# CAN.net
KiCad netlist of a schematic drawn in Altium Designer
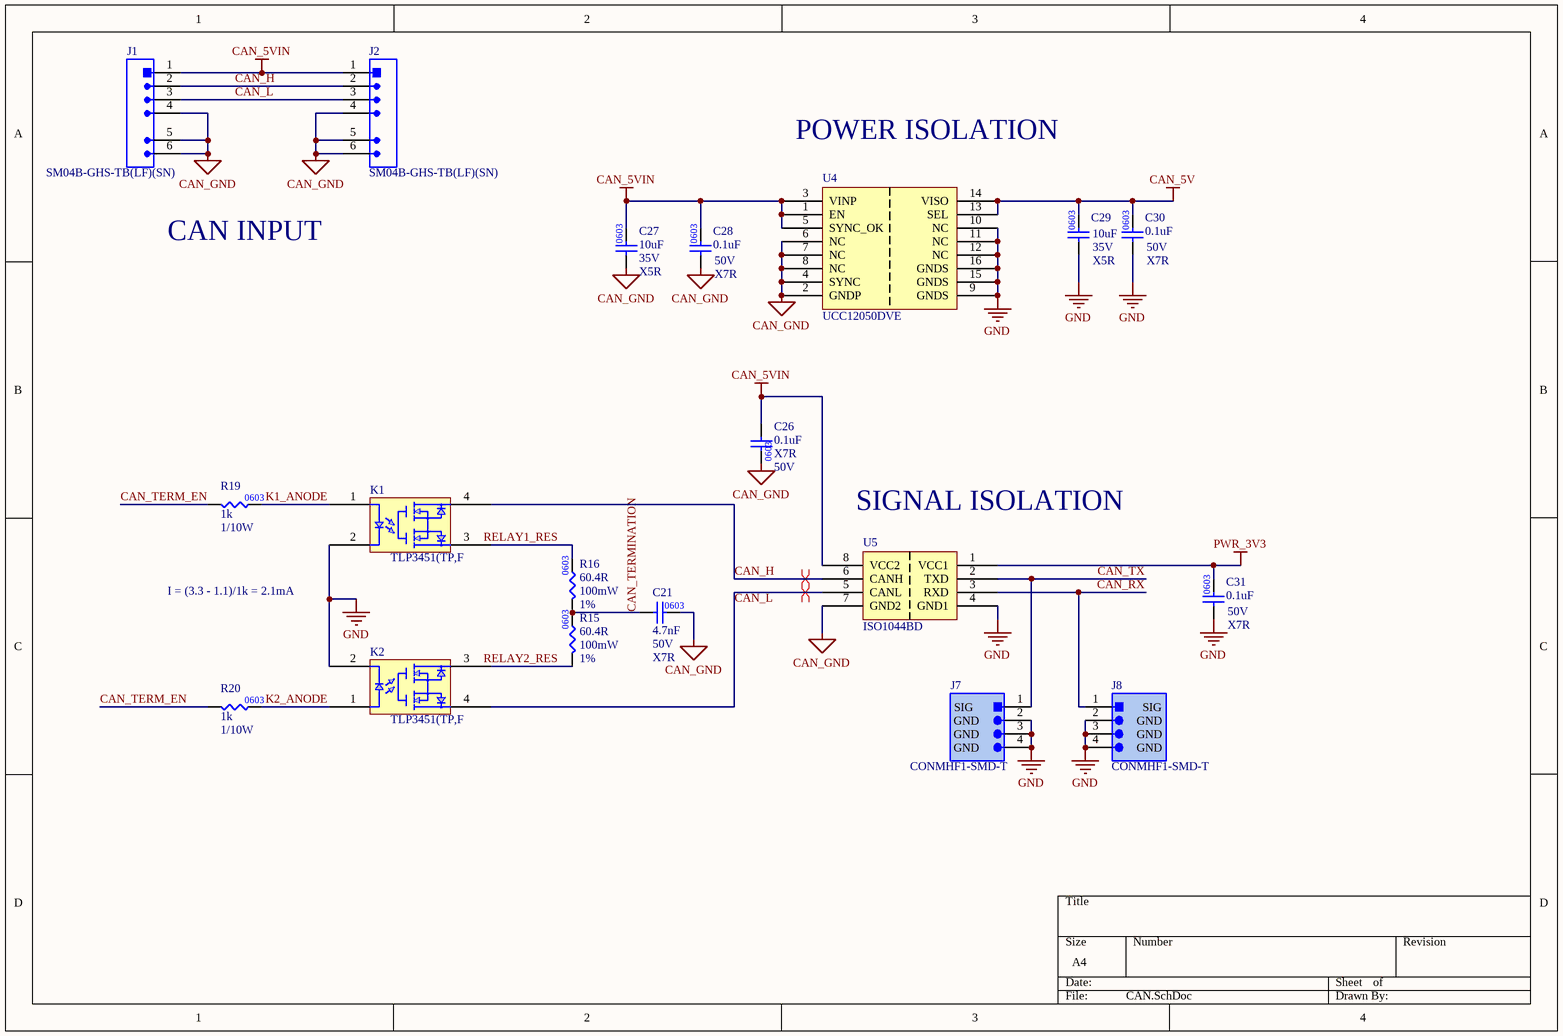
[diagram p0: CAN.SchDoc]

(export (version "E")
  (design (tool "Eeschema 10.0.6"))
  (components
    (comp (ref "C21")
      (value "4.7nF")
      (footprint ".CAP_0603-Footprint-1")
      (description "CAP CER 4700PF 50V X7R 0603")
      (fields
        (field (name "RATED DC VOLTAGE (URDC)") "50V")
        (field (name "TEMPERATURE CHARACTERISTICS CODE") "X7R")
        (field (name "Comment") "GCM188R71H472KA37D")
      )
      (libsource (lib "WARG") (part ".CAP_0603-Symbol-1"))
    )
    (comp (ref "C26")
      (value "0.1uF")
      (footprint ".CAP_0603-Footprint-1")
      (description "CAP CER 0.1uF 50V X7R 0603")
      (fields
        (field (name "DIELECTRIC") "X7R")
        (field (name "VOLTAGE") "50V")
        (field (name "TOLERANCE") "10%")
        (field (name "Comment") "GCM188R71H104KA57D")
      )
      (libsource (lib "WARG") (part ".CAP_0603-Symbol-1"))
    )
    (comp (ref "C27")
      (value "GRM188R6YA106MA73D")
      (footprint ".CAP_0603-Footprint-1")
      (description "CAP CER 10UF 35V X5R 0603")
      (fields
        (field (name "TOLERANCE") "±20%")
        (field (name "CAPACITANCE") "10uF")
        (field (name "VOLTAGE") "35V")
        (field (name "TEMPERATURE COEFFICIENT") "X5R")
      )
      (libsource (lib "WARG") (part ".CAP_0603-Symbol-1"))
    )
    (comp (ref "C28")
      (value "0.1uF")
      (footprint ".CAP_0603-Footprint-1")
      (description "CAP CER 0.1uF 50V X7R 0603")
      (fields
        (field (name "DIELECTRIC") "X7R")
        (field (name "VOLTAGE") "50V")
        (field (name "TOLERANCE") "10%")
        (field (name "Comment") "GCM188R71H104KA57D")
      )
      (libsource (lib "WARG") (part ".CAP_0603-Symbol-1"))
    )
    (comp (ref "C29")
      (value "GRM188R6YA106MA73D")
      (footprint ".CAP_0603-Footprint-1")
      (description "CAP CER 10UF 35V X5R 0603")
      (fields
        (field (name "TOLERANCE") "±20%")
        (field (name "CAPACITANCE") "10uF")
        (field (name "VOLTAGE") "35V")
        (field (name "TEMPERATURE COEFFICIENT") "X5R")
      )
      (libsource (lib "WARG") (part ".CAP_0603-Symbol-1"))
    )
    (comp (ref "C30")
      (value "0.1uF")
      (footprint ".CAP_0603-Footprint-1")
      (description "CAP CER 0.1uF 50V X7R 0603")
      (fields
        (field (name "DIELECTRIC") "X7R")
        (field (name "VOLTAGE") "50V")
        (field (name "TOLERANCE") "10%")
        (field (name "Comment") "GCM188R71H104KA57D")
      )
      (libsource (lib "WARG") (part ".CAP_0603-Symbol-1"))
    )
    (comp (ref "C31")
      (value "0.1uF")
      (footprint ".CAP_0603-Footprint-1")
      (description "CAP CER 0.1uF 50V X7R 0603")
      (fields
        (field (name "DIELECTRIC") "X7R")
        (field (name "VOLTAGE") "50V")
        (field (name "TOLERANCE") "10%")
        (field (name "Comment") "GCM188R71H104KA57D")
      )
      (libsource (lib "WARG") (part ".CAP_0603-Symbol-1"))
    )
    (comp (ref "J1")
      (value "SM04B-GHS-TB(LF)(SN)")
      (footprint "CONN_SM04B-GHS-TB_JST")
      (description "Conn Shrouded Header HDR 4 POS 1.25mm Solder RA SMD Reel")
      (libsource (lib "WARG") (part "SM04B-GHS-TB(LF)(SN)"))
    )
    (comp (ref "J2")
      (value "SM04B-GHS-TB(LF)(SN)")
      (footprint "CONN_SM04B-GHS-TB_JST")
      (description "Conn Shrouded Header HDR 4 POS 1.25mm Solder RA SMD Reel")
      (libsource (lib "") (part "SM04B-GHS-TB(LF)(SN)_1"))
    )
    (comp (ref "J7")
      (value "CONMHF1-SMD-T")
      (footprint "CONMHF1-SMD-T-Footprint-1")
      (description "CONN UMC JACK STR SMD")
      (libsource (lib "WARG") (part "CONMHF1-SMD-T-Symbol-1"))
    )
    (comp (ref "J8")
      (value "CONMHF1-SMD-T")
      (footprint "CONMHF1-SMD-T-Footprint-1")
      (description "CONN UMC JACK STR SMD")
      (libsource (lib "") (part "CONMHF1-SMD-T-Symbol-1_1"))
    )
    (comp (ref "K1")
      (value "TLP3451(TP,F")
      (footprint "TLP3451(TP,F-Footprint-1")
      (description "Solid State Relay 20MA 1.4V Dc-in Ac/dc-out 4-PIN Vson T/r")
      (libsource (lib "WARG") (part "TLP3451(TP,F-Symbol-1"))
    )
    (comp (ref "K2")
      (value "TLP3451(TP,F")
      (footprint "TLP3451(TP,F-Footprint-1")
      (description "Solid State Relay 20MA 1.4V Dc-in Ac/dc-out 4-PIN Vson T/r")
      (libsource (lib "WARG") (part "TLP3451(TP,F-Symbol-1"))
    )
    (comp (ref "R15")
      (value "60.4R")
      (footprint "RES0603")
      (description "RES 60.4 OHM 1% 1/10W 0603")
      (fields
        (field (name "TOLERANCE") "1%")
        (field (name "POWER") "100mW")
        (field (name "Comment") "RC0603FR-1360R4L")
      )
      (libsource (lib "WARG") (part "RES-2"))
    )
    (comp (ref "R16")
      (value "60.4R")
      (footprint "RES0603")
      (description "RES 60.4 OHM 1% 1/10W 0603")
      (fields
        (field (name "TOLERANCE") "1%")
        (field (name "POWER") "100mW")
        (field (name "Comment") "RC0603FR-1360R4L")
      )
      (libsource (lib "WARG") (part "RES-2"))
    )
    (comp (ref "R19")
      (value "1k")
      (footprint ".RES_0603-Footprint-1")
      (description "RES 1k OHM 1% 1/10W 0603")
      (fields
        (field (name "POWER") "1/10W")
        (field (name "TOLERANCE") "1%")
        (field (name "Comment") "RC0603FR-071KL")
      )
      (libsource (lib "WARG") (part ".RES_0603-Symbol-1"))
    )
    (comp (ref "R20")
      (value "1k")
      (footprint ".RES_0603-Footprint-1")
      (description "RES 1k OHM 1% 1/10W 0603")
      (fields
        (field (name "POWER") "1/10W")
        (field (name "TOLERANCE") "1%")
        (field (name "Comment") "RC0603FR-071KL")
      )
      (libsource (lib "WARG") (part ".RES_0603-Symbol-1"))
    )
    (comp (ref "U4")
      (value "UCC12050DVE")
      (footprint "16SOIC-Footprint")
      (description "DC DC CONVERTER 3.3V 5V 500MW")
      (libsource (lib "WARG") (part "UCC12050DVE-Symbol-1"))
    )
    (comp (ref "U5")
      (value "ISO1044BD")
      (footprint "8SOIC-Footprint-1")
      (description "Isolated CAN FD transceiver in small package 8-SOIC -40 to 125")
      (libsource (lib "WARG") (part "ISO1044BD-Symbol-1"))
    )
  )
  (nets
    (net (code "1") (name "/CAN_H") (class "Default")
      (node (ref "J1") (pin "2") (pinfunction "2_2") (pintype "passive"))
      (node (ref "J2") (pin "2") (pinfunction "2_2") (pintype "passive"))
      (node (ref "K1") (pin "4") (pinfunction "Drain_4") (pintype "passive"))
      (node (ref "U5") (pin "6") (pinfunction "CANH_6") (pintype "passive"))
    )
    (net (code "2") (name "/CAN_L") (class "Default")
      (node (ref "J1") (pin "3") (pinfunction "3_3") (pintype "passive"))
      (node (ref "J2") (pin "3") (pinfunction "3_3") (pintype "passive"))
      (node (ref "K2") (pin "4") (pinfunction "Drain_4") (pintype "passive"))
      (node (ref "U5") (pin "5") (pinfunction "CANL_5") (pintype "passive"))
    )
    (net (code "3") (name "/CAN_RX") (class "Default")
      (node (ref "J8") (pin "1") (pinfunction "SIG_1") (pintype "passive"))
      (node (ref "U5") (pin "3") (pinfunction "RXD_3") (pintype "passive"))
    )
    (net (code "4") (name "/CAN_TERMINATION") (class "Default")
      (node (ref "C21") (pin "1") (pinfunction "1_1") (pintype "passive"))
      (node (ref "R15") (pin "2") (pinfunction "2_2") (pintype "passive"))
      (node (ref "R16") (pin "1") (pinfunction "1_1") (pintype "passive"))
    )
    (net (code "5") (name "/CAN_TERM_EN") (class "Default")
      (node (ref "R19") (pin "1") (pinfunction "1_1") (pintype "passive"))
      (node (ref "R20") (pin "1") (pinfunction "1_1") (pintype "passive"))
    )
    (net (code "6") (name "/CAN_TX") (class "Default")
      (node (ref "J7") (pin "1") (pinfunction "SIG_1") (pintype "passive"))
      (node (ref "U5") (pin "2") (pinfunction "TXD_2") (pintype "passive"))
    )
    (net (code "7") (name "/K1_ANODE") (class "Default")
      (node (ref "K1") (pin "1") (pinfunction "Anode_1") (pintype "passive"))
      (node (ref "R19") (pin "2") (pinfunction "2_2") (pintype "passive"))
    )
    (net (code "8") (name "/K2_ANODE") (class "Default")
      (node (ref "K2") (pin "1") (pinfunction "Anode_1") (pintype "passive"))
      (node (ref "R20") (pin "2") (pinfunction "2_2") (pintype "passive"))
    )
    (net (code "9") (name "/RELAY1_RES") (class "Default")
      (node (ref "K1") (pin "3") (pinfunction "Drain_3") (pintype "passive"))
      (node (ref "R16") (pin "2") (pinfunction "2_2") (pintype "passive"))
    )
    (net (code "10") (name "/RELAY2_RES") (class "Default")
      (node (ref "K2") (pin "3") (pinfunction "Drain_3") (pintype "passive"))
      (node (ref "R15") (pin "1") (pinfunction "1_1") (pintype "passive"))
    )
    (net (code "11") (name "CAN_5V") (class "Default")
      (node (ref "C29") (pin "2") (pinfunction "2_2") (pintype "passive"))
      (node (ref "C30") (pin "2") (pinfunction "2_2") (pintype "passive"))
      (node (ref "U4") (pin "13") (pinfunction "SEL_13") (pintype "passive"))
      (node (ref "U4") (pin "14") (pinfunction "VISO_14") (pintype "passive"))
    )
    (net (code "12") (name "CAN_5VIN") (class "Default")
      (node (ref "C26") (pin "2") (pinfunction "2_2") (pintype "passive"))
      (node (ref "C27") (pin "2") (pinfunction "2_2") (pintype "passive"))
      (node (ref "C28") (pin "2") (pinfunction "2_2") (pintype "passive"))
      (node (ref "J1") (pin "1") (pinfunction "1_1") (pintype "passive"))
      (node (ref "J2") (pin "1") (pinfunction "1_1") (pintype "passive"))
      (node (ref "U4") (pin "1") (pinfunction "EN_1") (pintype "passive"))
      (node (ref "U4") (pin "3") (pinfunction "VINP_3") (pintype "passive"))
      (node (ref "U4") (pin "5") (pinfunction "SYNC_OK_5") (pintype "passive"))
      (node (ref "U5") (pin "8") (pinfunction "VCC2_8") (pintype "passive"))
    )
    (net (code "13") (name "CAN_GND") (class "Default")
      (node (ref "C21") (pin "2") (pinfunction "2_2") (pintype "passive"))
      (node (ref "C26") (pin "1") (pinfunction "1_1") (pintype "passive"))
      (node (ref "C27") (pin "1") (pinfunction "1_1") (pintype "passive"))
      (node (ref "C28") (pin "1") (pinfunction "1_1") (pintype "passive"))
      (node (ref "J1") (pin "4") (pinfunction "4_4") (pintype "passive"))
      (node (ref "J1") (pin "5") (pinfunction "5_5") (pintype "passive"))
      (node (ref "J1") (pin "6") (pinfunction "6_6") (pintype "passive"))
      (node (ref "J2") (pin "4") (pinfunction "4_4") (pintype "passive"))
      (node (ref "J2") (pin "5") (pinfunction "5_5") (pintype "passive"))
      (node (ref "J2") (pin "6") (pinfunction "6_6") (pintype "passive"))
      (node (ref "U4") (pin "2") (pinfunction "GNDP_2") (pintype "passive"))
      (node (ref "U4") (pin "4") (pinfunction "SYNC_4") (pintype "passive"))
      (node (ref "U4") (pin "6") (pinfunction "NC_6") (pintype "passive"))
      (node (ref "U4") (pin "7") (pinfunction "NC_7") (pintype "passive"))
      (node (ref "U4") (pin "8") (pinfunction "NC_8") (pintype "passive"))
      (node (ref "U5") (pin "7") (pinfunction "GND2_7") (pintype "passive"))
    )
    (net (code "14") (name "GND") (class "Default")
      (node (ref "C29") (pin "1") (pinfunction "1_1") (pintype "passive"))
      (node (ref "C30") (pin "1") (pinfunction "1_1") (pintype "passive"))
      (node (ref "C31") (pin "1") (pinfunction "1_1") (pintype "passive"))
      (node (ref "J7") (pin "2") (pinfunction "GND_2") (pintype "passive"))
      (node (ref "J7") (pin "3") (pinfunction "GND_3") (pintype "passive"))
      (node (ref "J7") (pin "4") (pinfunction "GND_4") (pintype "passive"))
      (node (ref "J8") (pin "2") (pinfunction "GND_2") (pintype "passive"))
      (node (ref "J8") (pin "3") (pinfunction "GND_3") (pintype "passive"))
      (node (ref "J8") (pin "4") (pinfunction "GND_4") (pintype "passive"))
      (node (ref "K1") (pin "2") (pinfunction "Cathode_2") (pintype "passive"))
      (node (ref "K2") (pin "2") (pinfunction "Cathode_2") (pintype "passive"))
      (node (ref "U4") (pin "10") (pinfunction "NC_10") (pintype "passive"))
      (node (ref "U4") (pin "11") (pinfunction "NC_11") (pintype "passive"))
      (node (ref "U4") (pin "12") (pinfunction "NC_12") (pintype "passive"))
      (node (ref "U4") (pin "15") (pinfunction "GNDS_15") (pintype "passive"))
      (node (ref "U4") (pin "16") (pinfunction "GNDS_16") (pintype "passive"))
      (node (ref "U4") (pin "9") (pinfunction "GNDS_9") (pintype "passive"))
      (node (ref "U5") (pin "4") (pinfunction "GND1_4") (pintype "passive"))
    )
    (net (code "15") (name "PWR_3V3") (class "Default")
      (node (ref "C31") (pin "2") (pinfunction "2_2") (pintype "passive"))
      (node (ref "U5") (pin "1") (pinfunction "VCC1_1") (pintype "passive"))
    )
  )
)
